# 04_Misc.net
KiCad netlist of a schematic drawn in Altium Designer
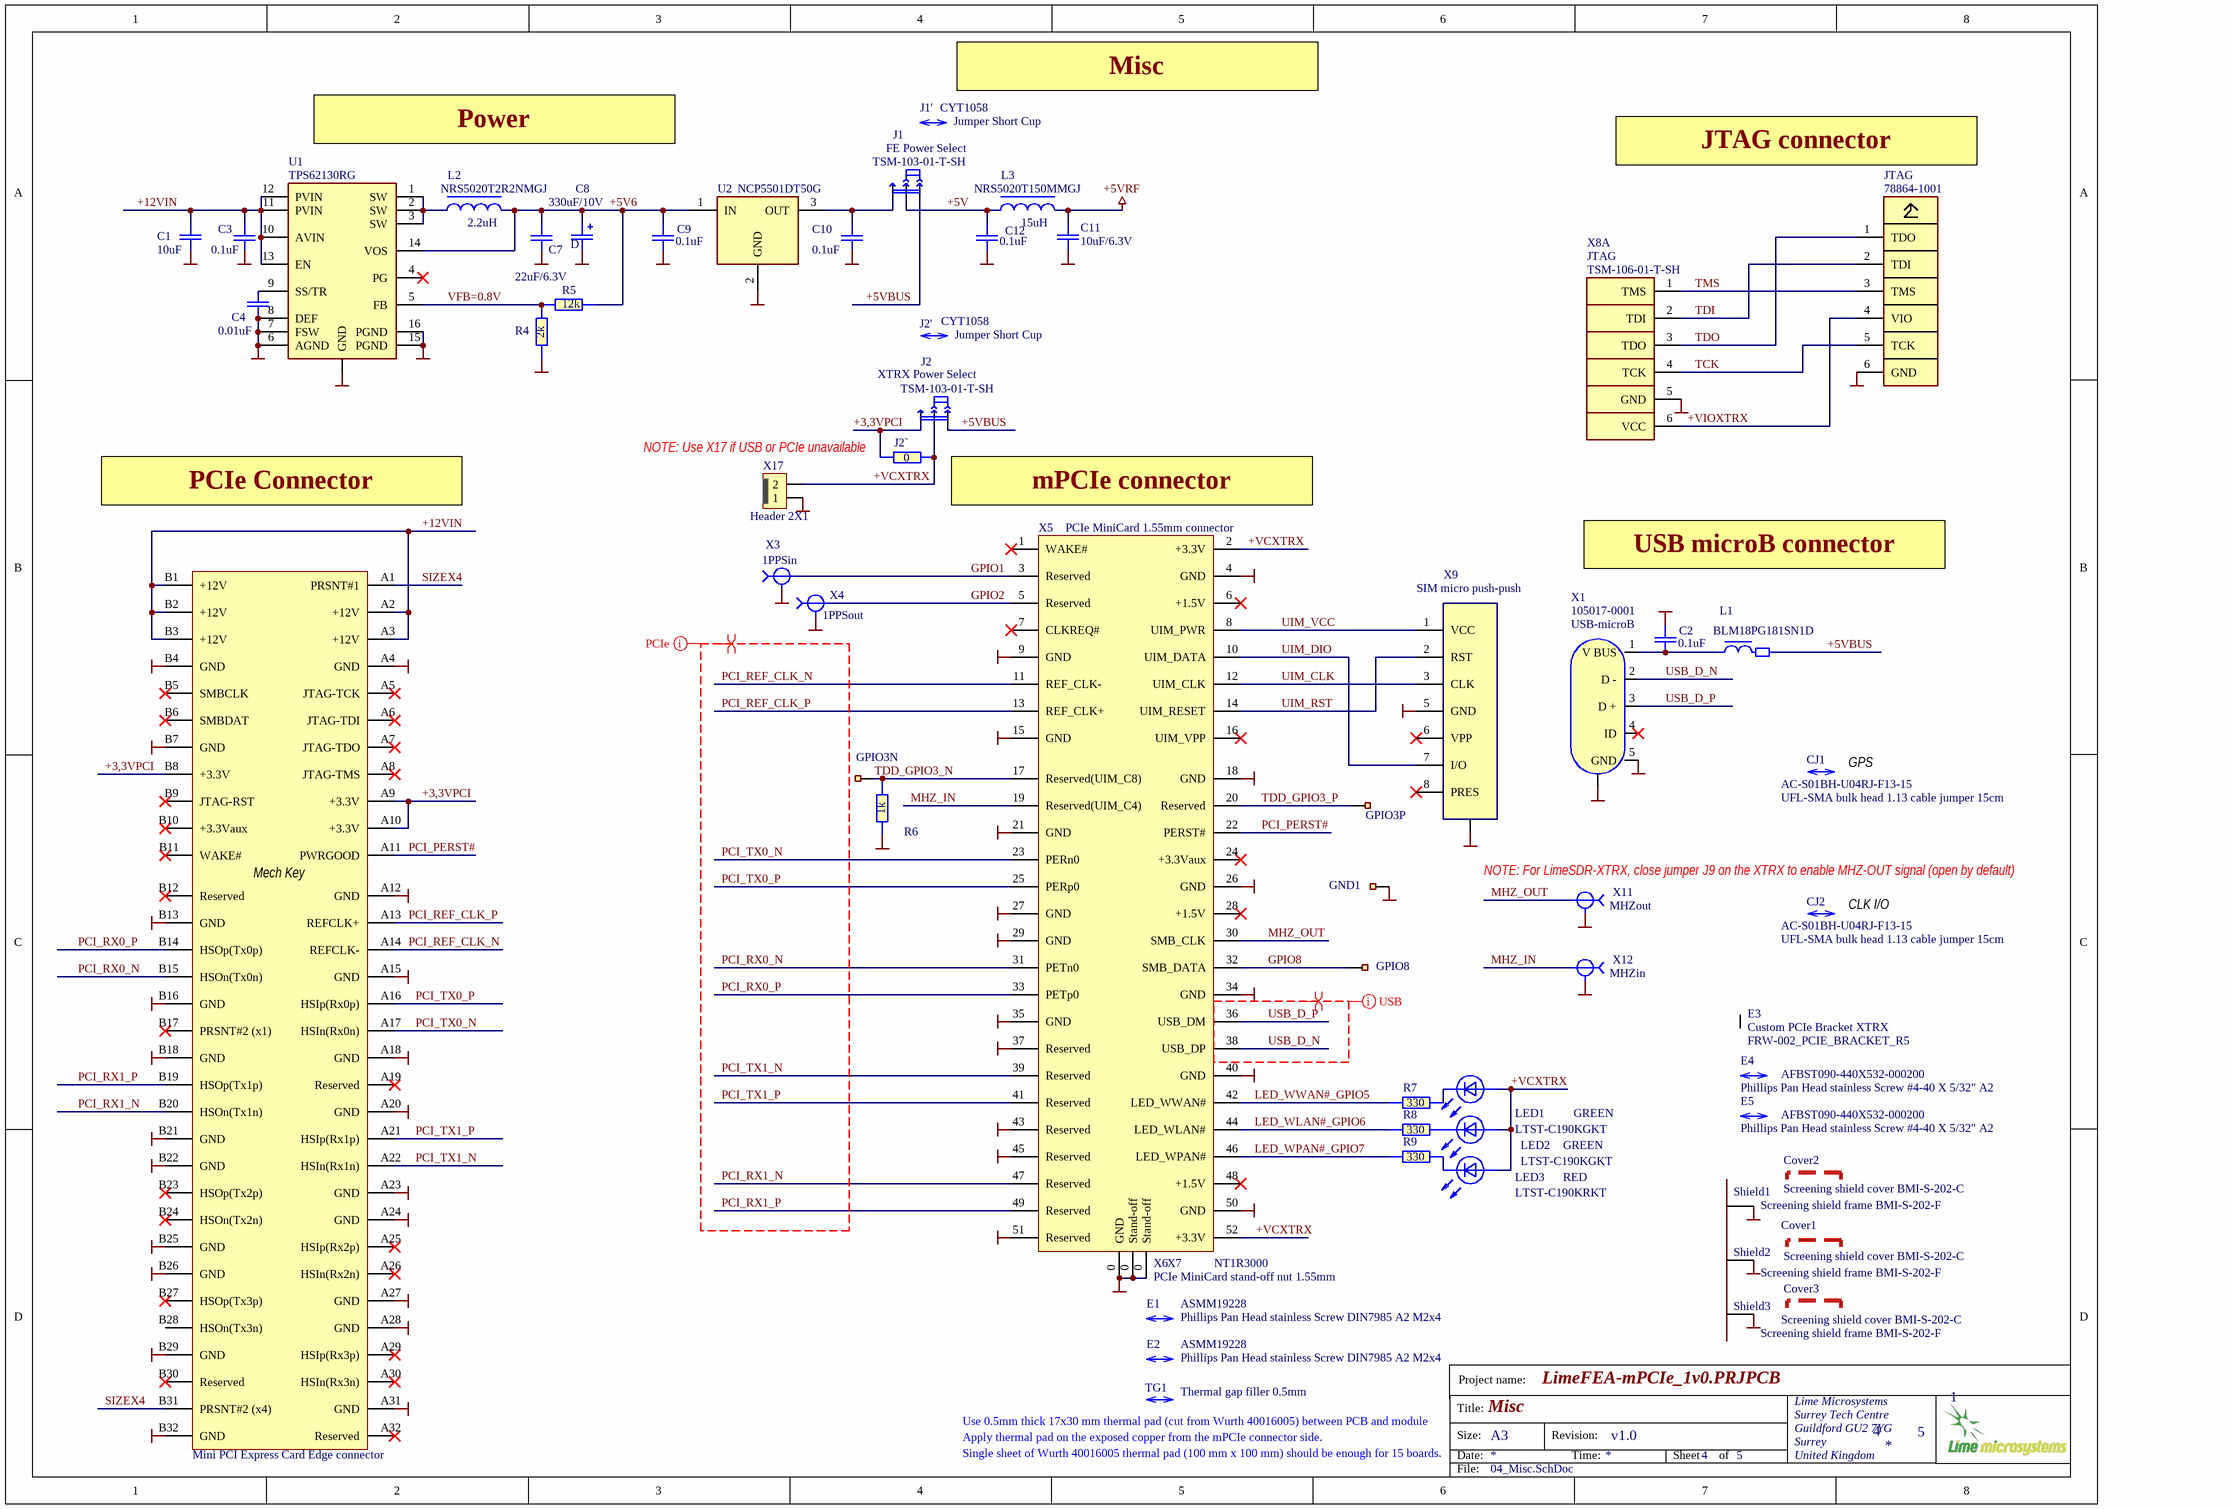
[diagram p0: 04_Misc.SchDoc]

(export (version "E")
  (design (tool "Eeschema 10.0.6"))
  (components
    (comp (ref "C1")
      (value "10uF")
      (footprint "C0805")
      (description "Capacitor")
      (fields (field (name "MANUFACTURER") "MURATA") (field (name "TOLERANCE") "20%"))
      (libsource (lib "Capacitors") (part "C0805"))
    )
    (comp (ref "C2")
      (value "0.1uF")
      (footprint "C0603-PHILLIPS")
      (description "Capacitor")
      (fields (field (name "MANUFACTURER") "MURATA") (field (name "TOLERANCE") "20%"))
      (libsource (lib "altium-import") (part "root_2_C0603_"))
    )
    (comp (ref "C3")
      (value "0.1uF")
      (footprint "C0603-PHILLIPS")
      (description "Capacitor")
      (fields (field (name "MANUFACTURER") "MURATA") (field (name "TOLERANCE") "20%"))
      (libsource (lib "altium-import") (part "root_2_C0603_"))
    )
    (comp (ref "C4")
      (value "0.01uF")
      (footprint "C0603-PHILLIPS")
      (description "Capacitor")
      (fields (field (name "MANUFACTURER") "MURATA") (field (name "TOLERANCE") "20%"))
      (libsource (lib "Capacitors") (part "C0603"))
    )
    (comp (ref "C7")
      (value "22uF/6.3V")
      (footprint "C0603-PHILLIPS")
      (description "Capacitor")
      (fields (field (name "MANUFACTURER") "MURATA") (field (name "TOLERANCE") "20%"))
      (libsource (lib "altium-import") (part "root_2_C0603_"))
    )
    (comp (ref "C8")
      (value "330uF/10V")
      (footprint "cd7343")
      (description "Capacitor")
      (fields (field (name "MANUFACTURER") "Kemet"))
      (libsource (lib "altium-import") (part "root_0_CD7343_"))
    )
    (comp (ref "C9")
      (value "0.1uF")
      (footprint "C0603-PHILLIPS")
      (description "Capacitor")
      (fields (field (name "MANUFACTURER") "MURATA") (field (name "TOLERANCE") "20%"))
      (libsource (lib "altium-import") (part "root_2_C0603_"))
    )
    (comp (ref "C10")
      (value "0.1uF")
      (footprint "C0603-PHILLIPS")
      (description "Capacitor")
      (fields (field (name "MANUFACTURER") "MURATA") (field (name "TOLERANCE") "20%"))
      (libsource (lib "altium-import") (part "root_2_C0603_"))
    )
    (comp (ref "C11")
      (value "10uF/6.3V")
      (footprint "C0603-Phillips")
      (description "Capacitor")
      (fields (field (name "MANUFACTURER") "MURATA") (field (name "TOLERANCE") "20%"))
      (libsource (lib "") (part "C0603_1"))
    )
    (comp (ref "C12")
      (value "0.1uF")
      (footprint "C0603-PHILLIPS")
      (description "Capacitor")
      (fields (field (name "MANUFACTURER") "MURATA") (field (name "TOLERANCE") "20%"))
      (libsource (lib "altium-import") (part "root_2_C0603_"))
    )
    (comp (ref "CJ1")
      (value "AC-S01BH-U04RJ-F13-15")
      (description "Cable jumper")
      (fields
        (field (name "MANUFACTURER") "RFSupplier")
        (field (name "MISC") "UFL-SMA bulk head 1.13 cable jumper 15cm")
      )
      (libsource (lib "LimeFEA-mPCIe_1v0") (part "Mating part"))
    )
    (comp (ref "CJ2")
      (value "AC-S01BH-U04RJ-F13-15")
      (description "Cable jumper")
      (fields
        (field (name "MANUFACTURER") "RFSupplier")
        (field (name "MISC") "UFL-SMA bulk head 1.13 cable jumper 15cm")
      )
      (libsource (lib "LimeFEA-mPCIe_1v0") (part "Mating part"))
    )
    (comp (ref "Cover1")
      (value "Screening shield cover BMI-S-202-C")
      (description "Screening shield cover")
      (fields (field (name "MANUFACTURER") "Laird Tech"))
      (libsource (lib "LimeFEA-mPCIe_1v0") (part "Screen cover BMI-S-202-C"))
    )
    (comp (ref "Cover2")
      (value "Screening shield cover BMI-S-202-C")
      (description "Screening shield cover")
      (fields (field (name "MANUFACTURER") "Laird Tech"))
      (libsource (lib "LimeFEA-mPCIe_1v0") (part "Screen cover BMI-S-202-C"))
    )
    (comp (ref "Cover3")
      (value "Screening shield cover BMI-S-202-C")
      (description "Screening shield cover")
      (fields (field (name "MANUFACTURER") "Laird Tech"))
      (libsource (lib "LimeFEA-mPCIe_1v0") (part "Screen cover BMI-S-202-C"))
    )
    (comp (ref "E1")
      (value "ASMM19228")
      (description "Screw M2")
      (fields
        (field (name "MANUFACTURER") "Aspen Fasteners")
        (field (name "MISC") "Phillips Pan Head stainless Screw DIN7985 A2 M2x4")
      )
      (libsource (lib "LimeFEA-mPCIe_1v0") (part "Mating subpart 1"))
    )
    (comp (ref "E2")
      (value "ASMM19228")
      (description "Screw M2")
      (fields
        (field (name "MANUFACTURER") "Aspen Fasteners")
        (field (name "MISC") "Phillips Pan Head stainless Screw DIN7985 A2 M2x4")
      )
      (libsource (lib "LimeFEA-mPCIe_1v0") (part "Mating subpart 1"))
    )
    (comp (ref "E3")
      (value "Custom PCIe Bracket XTRX")
      (footprint "Custom_PCIe_bracket_XTRX1")
      (description "CNC'ed enclosure component")
      (fields (field (name "ALTIUM_VALUE") "FRW-002_PCIE_BRACKET_R5"))
      (libsource (lib "LimeFEA-mPCIe_1v0") (part "PCI_Bracket_XTRX1"))
    )
    (comp (ref "E4")
      (value "AFBST090-440X532-000200")
      (description "Screw #4-40")
      (fields
        (field (name "MANUFACTURER") "Aspen Fasteners")
        (field (name "MISC") "Phillips Pan Head stainless Screw #4-40 X 5/32\" A2")
      )
      (libsource (lib "LimeFEA-mPCIe_1v0") (part "Mating subpart 1"))
    )
    (comp (ref "E5")
      (value "AFBST090-440X532-000200")
      (description "Screw #4-40")
      (fields
        (field (name "MANUFACTURER") "Aspen Fasteners")
        (field (name "MISC") "Phillips Pan Head stainless Screw #4-40 X 5/32\" A2")
      )
      (libsource (lib "LimeFEA-mPCIe_1v0") (part "Mating subpart 1"))
    )
    (comp (ref "GND1")
      (value "~")
      (footprint "KP-C_d1mm")
      (fields (field (name "MANUFACTURER") "PCB"))
      (libsource (lib "") (part "KP40X40_1"))
    )
    (comp (ref "GPIO3N")
      (value "~")
      (footprint "KP-C_d1mm")
      (fields (field (name "MANUFACTURER") "PCB"))
      (libsource (lib "") (part "KP40X40_1"))
    )
    (comp (ref "GPIO3P")
      (value "~")
      (footprint "KP-C_d1mm")
      (fields (field (name "MANUFACTURER") "PCB"))
      (libsource (lib "Connectors") (part "KP40X40"))
    )
    (comp (ref "GPIO8")
      (value "~")
      (footprint "KP-C_d1mm")
      (fields (field (name "MANUFACTURER") "PCB"))
      (libsource (lib "Connectors") (part "KP40X40"))
    )
    (comp (ref "J1")
      (value "TSM-103-01-T-SH")
      (footprint "Head_Male_3P_R/A_SMD")
      (description "Jumper 3 pin")
      (fields (field (name "MANUFACTURER") "Samtec") (field (name "ALTIUM_VALUE") "FE Power Select"))
      (libsource (lib "LimeFEA-mPCIe_1v0") (part "JUMPER_3P R/A SMD"))
    )
    (comp (ref "J1'")
      (value "CYT1058")
      (description "Jumper Short Cup")
      (fields (field (name "MISC") "Jumper Short Cup"))
      (libsource (lib "LimeFEA-mPCIe_1v0") (part "Mating part"))
    )
    (comp (ref "J2")
      (value "TSM-103-01-T-SH")
      (footprint "Head_Male_3P_R/A_SMD")
      (description "Jumper 3 pin")
      (fields (field (name "MANUFACTURER") "Samtec") (field (name "ALTIUM_VALUE") "XTRX Power Select"))
      (libsource (lib "LimeFEA-mPCIe_1v0") (part "JUMPER_3P R/A SMD"))
    )
    (comp (ref "J2'")
      (value "CYT1058")
      (description "Jumper Short Cup")
      (fields (field (name "MISC") "Jumper Short Cup"))
      (libsource (lib "Andy") (part "Mating part"))
    )
    (comp (ref "J2`")
      (value "0")
      (footprint "R0603-PHILLIPS")
      (description "Jumper")
      (fields (field (name "MANUFACTURER") "YAGEO") (field (name "TOLERANCE") "1%"))
      (libsource (lib "altium-import") (part "root_1_R0603_"))
    )
    (comp (ref "L1")
      (value "BLM18PG181SN1D")
      (footprint "TI160808-Phillips")
      (description "Ferrite Bead EMIFIL")
      (fields (field (name "MANUFACTURER") "MURATA"))
      (libsource (lib "LimeFEA-mPCIe_1v0") (part "EMI_BLM18"))
    )
    (comp (ref "L2")
      (value "2.2uH")
      (footprint "L-NRS5030")
      (description "Coil")
      (fields
        (field (name "MANUFACTURER") "Taiyo Yuden")
        (field (name "TOLERANCE") "20%")
        (field (name "NAME") "NRS5020T2R2NMGJ")
      )
      (libsource (lib "LimeFEA-mPCIe_1v0") (part "L-NRS50x0"))
    )
    (comp (ref "L3")
      (value "15uH")
      (footprint "L-NRS5030")
      (description "Coil")
      (fields
        (field (name "MANUFACTURER") "Taiyo Yuden")
        (field (name "TOLERANCE") "20%")
        (field (name "NAME") "NRS5020T150MMGJ")
      )
      (libsource (lib "LimeFEA-mPCIe_1v0") (part "L-NRS50x0"))
    )
    (comp (ref "LED1")
      (value "LTST-C190KGKT")
      (footprint "LED-0603GR")
      (description "LED GREEN")
      (fields (field (name "MANUFACTURER") "Lite-On Inc") (field (name "ALTIUM_VALUE") "GREEN"))
      (libsource (lib "LimeFEA-mPCIe_1v0") (part "LED0603GR_Lite-On"))
    )
    (comp (ref "LED2")
      (value "LTST-C190KGKT")
      (footprint "LED-0603GR")
      (description "LED GREEN")
      (fields (field (name "MANUFACTURER") "Lite-On Inc") (field (name "ALTIUM_VALUE") "GREEN"))
      (libsource (lib "LimeFEA-mPCIe_1v0") (part "LED0603GR_Lite-On"))
    )
    (comp (ref "LED3")
      (value "LTST-C190KRKT")
      (footprint "LED-0603RD")
      (description "LED RED")
      (fields (field (name "MANUFACTURER") "Lite-On Inc") (field (name "ALTIUM_VALUE") "RED"))
      (libsource (lib "LimeFEA-mPCIe_1v0") (part "LED0603RD_Lite-On"))
    )
    (comp (ref "R4")
      (value "2k")
      (footprint "R0603-PHILLIPS")
      (description "Resistor")
      (fields (field (name "MANUFACTURER") "YAGEO") (field (name "TOLERANCE") "1%"))
      (libsource (lib "") (part "R0603_1"))
    )
    (comp (ref "R5")
      (value "12k")
      (footprint "R0603-PHILLIPS")
      (description "Resistor")
      (fields (field (name "MANUFACTURER") "YAGEO") (field (name "TOLERANCE") "1%"))
      (libsource (lib "Resistors") (part "R0603"))
    )
    (comp (ref "R6")
      (value "1k")
      (footprint "R0603-PHILLIPS")
      (description "Resistor")
      (fields (field (name "MANUFACTURER") "YAGEO") (field (name "TOLERANCE") "1%"))
      (libsource (lib "altium-import") (part "root_2_R0603_"))
    )
    (comp (ref "R7")
      (value "330")
      (footprint "R0603-PHILLIPS")
      (description "Resistor")
      (fields (field (name "MANUFACTURER") "YAGEO") (field (name "TOLERANCE") "1%"))
      (libsource (lib "altium-import") (part "root_1_R0603_"))
    )
    (comp (ref "R8")
      (value "330")
      (footprint "R0603-PHILLIPS")
      (description "Resistor")
      (fields (field (name "MANUFACTURER") "YAGEO") (field (name "TOLERANCE") "1%"))
      (libsource (lib "altium-import") (part "root_1_R0603_"))
    )
    (comp (ref "R9")
      (value "330")
      (footprint "R0603-PHILLIPS")
      (description "Resistor")
      (fields (field (name "MANUFACTURER") "YAGEO") (field (name "TOLERANCE") "1%"))
      (libsource (lib "altium-import") (part "root_1_R0603_"))
    )
    (comp (ref "Shield1")
      (value "Screening shield frame BMI-S-202-F")
      (footprint "BMI-S-202-F")
      (description "Screening shield frame")
      (fields (field (name "MANUFACTURER") "Laird Tech"))
      (libsource (lib "LimeFEA-mPCIe_1v0") (part "Screen frame BMI-S-202-F"))
    )
    (comp (ref "Shield2")
      (value "Screening shield frame BMI-S-202-F")
      (footprint "BMI-S-202-F")
      (description "Screening shield frame")
      (fields (field (name "MANUFACTURER") "Laird Tech"))
      (libsource (lib "LimeFEA-mPCIe_1v0") (part "Screen frame BMI-S-202-F"))
    )
    (comp (ref "Shield3")
      (value "Screening shield frame BMI-S-202-F")
      (footprint "BMI-S-202-F")
      (description "Screening shield frame")
      (fields (field (name "MANUFACTURER") "Laird Tech"))
      (libsource (lib "LimeFEA-mPCIe_1v0") (part "Screen frame BMI-S-202-F"))
    )
    (comp (ref "TG1")
      (value "The thermal pad with a size of 100 mm x 100 mm is to be cut in 17 mm x 30 mm pieces (resulting in a possible total of 15 pcs. from a single whole pad). A single assembled PCB requires 1 pcs. of 17 mm x 30 mm pad per 1 board. Calculate the number of whole thermal pad (P/N 40016005) pieces based on the assembled board batch size, rounding this number to whole pad pieces. Example: 5 pcs. PCB batch requires 1 pcs. of thermal pad (P/N 40016005) with leftovers. 300 pcs. PCB batch requires 20 pcs. of thermal pads (P/N 40016005) without leftovers.")
      (description "Thermal gap filler")
      (fields
        (field (name "MANUFACTURER") "Würth Elektronik")
        (field (name "MISC") "Thermal gap filler 0.5mm")
      )
      (libsource (lib "LimeFEA-mPCIe_1v0") (part "Mating subpart 1"))
    )
    (comp (ref "U1")
      (value "TPS62130RG")
      (footprint "QFN16(3x3/0/5mm)-Case485AE")
      (description "IC")
      (fields (field (name "MANUFACTURER") "TI"))
      (libsource (lib "LimeFEA-mPCIe_1v0") (part "TPS6213x"))
    )
    (comp (ref "U2")
      (value "NCP5501DT50G")
      (footprint "DPAK-3")
      (description "IC LDO fixed Vo")
      (fields (field (name "MANUFACTURER") "ON Semi"))
      (libsource (lib "LimeFEA-mPCIe_1v0") (part "NCP5501DTxxG"))
    )
    (comp (ref "X1")
      (value "105017-0001")
      (footprint "USB-micro-B")
      (description "Connector microUSB-B")
      (fields (field (name "MANUFACTURER") "MOLEX") (field (name "NAME") "USB-microB"))
      (libsource (lib "LimeFEA-mPCIe_1v0") (part "USB-microB_105017-1"))
    )
    (comp (ref "X2")
      (value "Mini PCI Express Card Edge connector")
      (footprint "PCIe x4 edge connector")
      (description "PCIe x4 Card edge connector")
      (libsource (lib "LimeFEA-mPCIe_1v0") (part "PCIe x4 Card"))
    )
    (comp (ref "X3")
      (value "0734120110")
      (footprint "U_FL")
      (description "Connector (UMCC)")
      (fields (field (name "MANUFACTURER") "Molex") (field (name "MISC") "1PPSin"))
      (libsource (lib "LimeFEA-mPCIe_1v0") (part "U_FL"))
    )
    (comp (ref "X4")
      (value "0734120110")
      (footprint "U_FL")
      (description "Connector (UMCC)")
      (fields (field (name "MANUFACTURER") "Molex") (field (name "MISC") "1PPSout"))
      (libsource (lib "LimeFEA-mPCIe_1v0") (part "U_FL"))
    )
    (comp (ref "X5")
      (value "PCIe MiniCard 1.55mm connector")
      (footprint "PCIe MiniCard 1.55mm conn")
      (description "Connector PCIe MiniCard")
      (fields (field (name "MANUFACTURER") "JAE Electronics"))
      (libsource (lib "LimeFEA-mPCIe_1v0") (part "PCIe MiniCard conn h1.55mm"))
    )
    (comp (ref "X6")
      (value "NT1R3000")
      (footprint "PCIe MiniCard 1.55mm stand off nut")
      (description "Stand-off nut PCIe MiniCard")
      (fields
        (field (name "MANUFACTURER") "JAE Electronics")
        (field (name "MISC") "PCIe MiniCard stand-off nut 1.55mm")
      )
      (libsource (lib "LimeFEA-mPCIe_1v0") (part "PCIe MiniCard nut h1.55mm"))
    )
    (comp (ref "X7")
      (value "NT1R3000")
      (footprint "PCIe MiniCard 1.55mm stand off nut")
      (description "Stand-off nut PCIe MiniCard")
      (fields (field (name "MANUFACTURER") "JAE Electronics"))
      (libsource (lib "LimeFEA-mPCIe_1v0") (part "PCIe MiniCard nut h1.55mm"))
    )
    (comp (ref "X8")
      (value "TSM-106-01-T-SH")
      (footprint "Head_Male_6P_R/A_SMD")
      (description "Connector header male")
      (fields (field (name "MANUFACTURER") "Samtec") (field (name "ALTIUM_VALUE") "JTAG"))
      (libsource (lib "LimeFEA-mPCIe_1v0") (part "Conn TSM-106-01-T-SH (=M20-89605)"))
    )
    (comp (ref "X9")
      (value "SIM micro push-push")
      (footprint "SIM_SF56S006V4BR2000-dig")
      (description "Connector SIM micro card")
      (fields (field (name "MANUFACTURER") "JAE"))
      (libsource (lib "LimeFEA-mPCIe_1v0") (part "SIM micro push-push"))
    )
    (comp (ref "X10")
      (value "JTAG")
      (footprint "Molex 78864-1001")
      (description "Connector board to board")
      (fields (field (name "MANUFACTURER") "Molex") (field (name "NAME") "78864-1001"))
      (libsource (lib "LimeFEA-mPCIe_1v0") (part "Conn Molex_788641001"))
    )
    (comp (ref "X11")
      (value "0734120110")
      (footprint "U_FL")
      (description "Connector (UMCC)")
      (fields (field (name "MANUFACTURER") "Molex") (field (name "MISC") "MHZout"))
      (libsource (lib "LimeFEA-mPCIe_1v0") (part "U_FL"))
    )
    (comp (ref "X12")
      (value "0734120110")
      (footprint "U_FL")
      (description "Connector (UMCC)")
      (fields (field (name "MANUFACTURER") "Molex") (field (name "MISC") "MHZin"))
      (libsource (lib "LimeFEA-mPCIe_1v0") (part "U_FL"))
    )
    (comp (ref "X17")
      (value "Header 2X1")
      (footprint "Header1x2_TH_LOCKING")
      (description "Headers & Wire Housings KK 100 Hdr FrLk Vert 02 Ckt Gold")
      (fields (field (name "MANUFACTURER PART NUMBER") "22-11-2026") (field (name "MANUFACTURER") "Molex"))
      (libsource (lib "LimeMicroAltiumLib_schLib_r04") (part "Header 2X1 LOCK"))
    )
  )
  (nets
    (net (code "1") (name "+5VRF") (class "Default")
      (node (ref "C11") (pin "2") (pinfunction "2_2") (pintype "passive"))
      (node (ref "L3") (pin "2") (pinfunction "2_2") (pintype "passive"))
    )
    (net (code "2") (name "/+3,3VPCI") (class "Default")
      (node (ref "J2") (pin "3") (pinfunction "3_3") (pintype "passive"))
      (node (ref "J2`") (pin "1") (pinfunction "1_1") (pintype "passive"))
      (node (ref "X2") (pin "A10") (pinfunction "+3.3V_A10") (pintype "passive"))
      (node (ref "X2") (pin "A9") (pinfunction "+3.3V_A9") (pintype "passive"))
      (node (ref "X2") (pin "B8") (pinfunction "+3.3V_B8") (pintype "passive"))
    )
    (net (code "3") (name "/+5V") (class "Default")
      (node (ref "C12") (pin "2") (pinfunction "2_2") (pintype "passive"))
      (node (ref "J1") (pin "2") (pinfunction "2_2") (pintype "passive"))
      (node (ref "L3") (pin "1") (pinfunction "1_1") (pintype "passive"))
    )
    (net (code "4") (name "/+5V6") (class "Default")
      (node (ref "C7") (pin "2") (pinfunction "2_2") (pintype "passive"))
      (node (ref "C8") (pin "1") (pinfunction "+_1") (pintype "passive"))
      (node (ref "C9") (pin "2") (pinfunction "2_2") (pintype "passive"))
      (node (ref "L2") (pin "2") (pinfunction "2_2") (pintype "passive"))
      (node (ref "R5") (pin "2") (pinfunction "2_2") (pintype "passive"))
      (node (ref "U1") (pin "14") (pinfunction "VOS_14") (pintype "passive"))
      (node (ref "U2") (pin "1") (pinfunction "IN_1") (pintype "passive"))
    )
    (net (code "5") (name "/+5VBUS") (class "Default")
      (node (ref "J1") (pin "1") (pinfunction "1_1") (pintype "passive"))
      (node (ref "J2") (pin "1") (pinfunction "1_1") (pintype "passive"))
      (node (ref "L1") (pin "2") (pinfunction "2_2") (pintype "passive"))
    )
    (net (code "6") (name "/+12VIN") (class "Default")
      (node (ref "C1") (pin "1") (pinfunction "1_1") (pintype "passive"))
      (node (ref "C3") (pin "2") (pinfunction "2_2") (pintype "passive"))
      (node (ref "U1") (pin "10") (pinfunction "AVIN_10") (pintype "passive"))
      (node (ref "U1") (pin "11") (pinfunction "PVIN_11") (pintype "passive"))
      (node (ref "U1") (pin "12") (pinfunction "PVIN_12") (pintype "passive"))
      (node (ref "U1") (pin "13") (pinfunction "EN_13") (pintype "passive"))
      (node (ref "X2") (pin "A2") (pinfunction "+12V_A2") (pintype "passive"))
      (node (ref "X2") (pin "A3") (pinfunction "+12V_A3") (pintype "passive"))
      (node (ref "X2") (pin "B1") (pinfunction "+12V_B1") (pintype "passive"))
      (node (ref "X2") (pin "B2") (pinfunction "+12V_B2") (pintype "passive"))
      (node (ref "X2") (pin "B3") (pinfunction "+12V_B3") (pintype "passive"))
    )
    (net (code "7") (name "/+VCXTRX") (class "Default")
      (node (ref "J2") (pin "2") (pinfunction "2_2") (pintype "passive"))
      (node (ref "J2`") (pin "2") (pinfunction "2_2") (pintype "passive"))
      (node (ref "LED1") (pin "2") (pinfunction "A_2") (pintype "passive"))
      (node (ref "LED2") (pin "2") (pinfunction "A_2") (pintype "passive"))
      (node (ref "LED3") (pin "2") (pinfunction "A_2") (pintype "passive"))
      (node (ref "X17") (pin "2") (pinfunction "2_2") (pintype "passive"))
      (node (ref "X5") (pin "2") (pinfunction "+3.3V_2") (pintype "passive"))
      (node (ref "X5") (pin "52") (pinfunction "+3.3V_52") (pintype "passive"))
    )
    (net (code "8") (name "/+VIOXTRX") (class "Default")
      (node (ref "X10") (pin "4") (pinfunction "VIO_4") (pintype "passive"))
      (node (ref "X8") (pin "6") (pinfunction "TMS_6") (pintype "passive"))
    )
    (net (code "9") (name "/GPIO1") (class "Default")
      (node (ref "X3") (pin "1") (pinfunction "1_1") (pintype "passive"))
      (node (ref "X5") (pin "3") (pinfunction "Reserved_3") (pintype "passive"))
    )
    (net (code "10") (name "/GPIO2") (class "Default")
      (node (ref "X4") (pin "1") (pinfunction "1_1") (pintype "passive"))
      (node (ref "X5") (pin "5") (pinfunction "Reserved_5") (pintype "passive"))
    )
    (net (code "11") (name "/GPIO8") (class "Default")
      (node (ref "GPIO8") (pin "1") (pinfunction "1_1") (pintype "passive"))
      (node (ref "X5") (pin "32") (pinfunction "SMB_DATA_32") (pintype "passive"))
    )
    (net (code "12") (name "/LED_WLAN#_GPIO6") (class "Default")
      (node (ref "R8") (pin "1") (pinfunction "1_1") (pintype "passive"))
      (node (ref "X5") (pin "44") (pinfunction "LED_WLAN#_44") (pintype "passive"))
    )
    (net (code "13") (name "/LED_WPAN#_GPIO7") (class "Default")
      (node (ref "R9") (pin "1") (pinfunction "1_1") (pintype "passive"))
      (node (ref "X5") (pin "46") (pinfunction "LED_WPAN#_46") (pintype "passive"))
    )
    (net (code "14") (name "/LED_WWAN#_GPIO5") (class "Default")
      (node (ref "R7") (pin "1") (pinfunction "1_1") (pintype "passive"))
      (node (ref "X5") (pin "42") (pinfunction "LED_WWAN#_42") (pintype "passive"))
    )
    (net (code "15") (name "/MHZ_IN") (class "Default")
      (node (ref "X12") (pin "1") (pinfunction "1_1") (pintype "passive"))
      (node (ref "X5") (pin "19") (pinfunction "Reserved(UIM_C4)_19") (pintype "passive"))
    )
    (net (code "16") (name "/MHZ_OUT") (class "Default")
      (node (ref "X11") (pin "1") (pinfunction "1_1") (pintype "passive"))
      (node (ref "X5") (pin "30") (pinfunction "SMB_CLK_30") (pintype "passive"))
    )
    (net (code "17") (name "/PCI_PERST#") (class "Default")
      (node (ref "X2") (pin "A11") (pinfunction "PWRGOOD_A11") (pintype "passive"))
      (node (ref "X5") (pin "22") (pinfunction "PERST#_22") (pintype "passive"))
    )
    (net (code "18") (name "/PCI_REF_CLK_N") (class "Default")
      (node (ref "X2") (pin "A14") (pinfunction "REFCLK-_A14") (pintype "passive"))
      (node (ref "X5") (pin "11") (pinfunction "REF_CLK-_11") (pintype "passive"))
    )
    (net (code "19") (name "/PCI_REF_CLK_P") (class "Default")
      (node (ref "X2") (pin "A13") (pinfunction "REFCLK+_A13") (pintype "passive"))
      (node (ref "X5") (pin "13") (pinfunction "REF_CLK+_13") (pintype "passive"))
    )
    (net (code "20") (name "/PCI_RX0_N") (class "Default")
      (node (ref "X2") (pin "B15") (pinfunction "HSOn(Tx0n)_B15") (pintype "passive"))
      (node (ref "X5") (pin "31") (pinfunction "PETn0_31") (pintype "passive"))
    )
    (net (code "21") (name "/PCI_RX0_P") (class "Default")
      (node (ref "X2") (pin "B14") (pinfunction "HSOp(Tx0p)_B14") (pintype "passive"))
      (node (ref "X5") (pin "33") (pinfunction "PETp0_33") (pintype "passive"))
    )
    (net (code "22") (name "/PCI_RX1_N") (class "Default")
      (node (ref "X2") (pin "B20") (pinfunction "HSOn(Tx1n)_B20") (pintype "passive"))
      (node (ref "X5") (pin "47") (pinfunction "Reserved_47") (pintype "passive"))
    )
    (net (code "23") (name "/PCI_RX1_P") (class "Default")
      (node (ref "X2") (pin "B19") (pinfunction "HSOp(Tx1p)_B19") (pintype "passive"))
      (node (ref "X5") (pin "49") (pinfunction "Reserved_49") (pintype "passive"))
    )
    (net (code "24") (name "/PCI_TX0_N") (class "Default")
      (node (ref "X2") (pin "A17") (pinfunction "HSIn(Rx0n)_A17") (pintype "passive"))
      (node (ref "X5") (pin "23") (pinfunction "PERn0_23") (pintype "passive"))
    )
    (net (code "25") (name "/PCI_TX0_P") (class "Default")
      (node (ref "X2") (pin "A16") (pinfunction "HSIp(Rx0p)_A16") (pintype "passive"))
      (node (ref "X5") (pin "25") (pinfunction "PERp0_25") (pintype "passive"))
    )
    (net (code "26") (name "/PCI_TX1_N") (class "Default")
      (node (ref "X2") (pin "A22") (pinfunction "HSIn(Rx1n)_A22") (pintype "passive"))
      (node (ref "X5") (pin "39") (pinfunction "Reserved_39") (pintype "passive"))
    )
    (net (code "27") (name "/PCI_TX1_P") (class "Default")
      (node (ref "X2") (pin "A21") (pinfunction "HSIp(Rx1p)_A21") (pintype "passive"))
      (node (ref "X5") (pin "41") (pinfunction "Reserved_41") (pintype "passive"))
    )
    (net (code "28") (name "/SIZEX4") (class "Default")
      (node (ref "X2") (pin "A1") (pinfunction "PRSNT#1_A1") (pintype "passive"))
      (node (ref "X2") (pin "B31") (pinfunction "PRSNT#2_(x4)_B31") (pintype "passive"))
    )
    (net (code "29") (name "/TCK") (class "Default")
      (node (ref "X10") (pin "5") (pinfunction "TCK_5") (pintype "passive"))
      (node (ref "X8") (pin "4") (pinfunction "TCK_4") (pintype "passive"))
    )
    (net (code "30") (name "/TDD_GPIO3_N") (class "Default")
      (node (ref "GPIO3N") (pin "1") (pinfunction "1_1") (pintype "passive"))
      (node (ref "R6") (pin "2") (pinfunction "2_2") (pintype "passive"))
      (node (ref "X5") (pin "17") (pinfunction "Reserved(UIM_C8)_17") (pintype "passive"))
    )
    (net (code "31") (name "/TDD_GPIO3_P") (class "Default")
      (node (ref "GPIO3P") (pin "1") (pinfunction "1_1") (pintype "passive"))
      (node (ref "X5") (pin "20") (pinfunction "Reserved_20") (pintype "passive"))
    )
    (net (code "32") (name "/TDI") (class "Default")
      (node (ref "X10") (pin "2") (pinfunction "TDI_2") (pintype "passive"))
      (node (ref "X8") (pin "2") (pinfunction "GND_2") (pintype "passive"))
    )
    (net (code "33") (name "/TDO") (class "Default")
      (node (ref "X10") (pin "1") (pinfunction "TDO_1") (pintype "passive"))
      (node (ref "X8") (pin "3") (pinfunction "TCK_3") (pintype "passive"))
    )
    (net (code "34") (name "/TMS") (class "Default")
      (node (ref "X10") (pin "3") (pinfunction "TMS_3") (pintype "passive"))
      (node (ref "X8") (pin "1") (pinfunction "VCC_1") (pintype "passive"))
    )
    (net (code "35") (name "/UIM_CLK") (class "Default")
      (node (ref "X5") (pin "12") (pinfunction "UIM_CLK_12") (pintype "passive"))
      (node (ref "X9") (pin "3") (pinfunction "CLK_3") (pintype "passive"))
    )
    (net (code "36") (name "/UIM_DIO") (class "Default")
      (node (ref "X5") (pin "10") (pinfunction "UIM_DATA_10") (pintype "passive"))
      (node (ref "X9") (pin "7") (pinfunction "I/O_7") (pintype "passive"))
    )
    (net (code "37") (name "/UIM_RST") (class "Default")
      (node (ref "X5") (pin "14") (pinfunction "UIM_RESET_14") (pintype "passive"))
      (node (ref "X9") (pin "2") (pinfunction "RST_2") (pintype "passive"))
    )
    (net (code "38") (name "/UIM_VCC") (class "Default")
      (node (ref "X5") (pin "8") (pinfunction "UIM_PWR_8") (pintype "passive"))
      (node (ref "X9") (pin "1") (pinfunction "VCC_1") (pintype "passive"))
    )
    (net (code "39") (name "/USB_D_N") (class "Default")
      (node (ref "X1") (pin "2") (pinfunction "D_-_2") (pintype "passive"))
      (node (ref "X5") (pin "38") (pinfunction "USB_DP_38") (pintype "passive"))
    )
    (net (code "40") (name "/USB_D_P") (class "Default")
      (node (ref "X1") (pin "3") (pinfunction "D_+_3") (pintype "passive"))
      (node (ref "X5") (pin "36") (pinfunction "USB_DM_36") (pintype "passive"))
    )
    (net (code "41") (name "GND") (class "Default")
      (node (ref "C1") (pin "2") (pinfunction "2_2") (pintype "passive"))
      (node (ref "C10") (pin "1") (pinfunction "1_1") (pintype "passive"))
      (node (ref "C11") (pin "1") (pinfunction "1_1") (pintype "passive"))
      (node (ref "C12") (pin "1") (pinfunction "1_1") (pintype "passive"))
      (node (ref "C2") (pin "2") (pinfunction "2_2") (pintype "passive"))
      (node (ref "C3") (pin "1") (pinfunction "1_1") (pintype "passive"))
      (node (ref "C4") (pin "2") (pinfunction "2_2") (pintype "passive"))
      (node (ref "C7") (pin "1") (pinfunction "1_1") (pintype "passive"))
      (node (ref "C8") (pin "2") (pinfunction "-_2") (pintype "passive"))
      (node (ref "C9") (pin "1") (pinfunction "1_1") (pintype "passive"))
      (node (ref "GND1") (pin "1") (pinfunction "1_1") (pintype "passive"))
      (node (ref "R4") (pin "2") (pinfunction "2_2") (pintype "passive"))
      (node (ref "R6") (pin "1") (pinfunction "1_1") (pintype "passive"))
      (node (ref "Shield1") (pin "0") (pinfunction "GND_0") (pintype "passive"))
      (node (ref "Shield2") (pin "0") (pinfunction "GND_0") (pintype "passive"))
      (node (ref "Shield3") (pin "0") (pinfunction "GND_0") (pintype "passive"))
      (node (ref "U1") (pin "0") (pinfunction "GND_0") (pintype "passive"))
      (node (ref "U1") (pin "15") (pinfunction "PGND_15") (pintype "passive"))
      (node (ref "U1") (pin "16") (pinfunction "PGND_16") (pintype "passive"))
      (node (ref "U1") (pin "6") (pinfunction "AGND_6") (pintype "passive"))
      (node (ref "U1") (pin "7") (pinfunction "FSW_7") (pintype "passive"))
      (node (ref "U1") (pin "8") (pinfunction "DEF_8") (pintype "passive"))
      (node (ref "U2") (pin "2") (pinfunction "GND_2") (pintype "passive"))
      (node (ref "X1") (pin "0") (pinfunction "GND_0") (pintype "passive"))
      (node (ref "X1") (pin "5") (pinfunction "GND_5") (pintype "passive"))
      (node (ref "X10") (pin "6") (pinfunction "GND_6") (pintype "passive"))
      (node (ref "X11") (pin "2") (pinfunction "GND_2") (pintype "passive"))
      (node (ref "X12") (pin "2") (pinfunction "GND_2") (pintype "passive"))
      (node (ref "X17") (pin "1") (pinfunction "1_1") (pintype "passive"))
      (node (ref "X2") (pin "A12") (pinfunction "GND_A12") (pintype "passive"))
      (node (ref "X2") (pin "A15") (pinfunction "GND_A15") (pintype "passive"))
      (node (ref "X2") (pin "A18") (pinfunction "GND_A18") (pintype "passive"))
      (node (ref "X2") (pin "A20") (pinfunction "GND_A20") (pintype "passive"))
      (node (ref "X2") (pin "A23") (pinfunction "GND_A23") (pintype "passive"))
      (node (ref "X2") (pin "A24") (pinfunction "GND_A24") (pintype "passive"))
      (node (ref "X2") (pin "A27") (pinfunction "GND_A27") (pintype "passive"))
      (node (ref "X2") (pin "A28") (pinfunction "GND_A28") (pintype "passive"))
      (node (ref "X2") (pin "A31") (pinfunction "GND_A31") (pintype "passive"))
      (node (ref "X2") (pin "A4") (pinfunction "GND_A4") (pintype "passive"))
      (node (ref "X2") (pin "B13") (pinfunction "GND_B13") (pintype "passive"))
      (node (ref "X2") (pin "B16") (pinfunction "GND_B16") (pintype "passive"))
      (node (ref "X2") (pin "B18") (pinfunction "GND_B18") (pintype "passive"))
      (node (ref "X2") (pin "B21") (pinfunction "GND_B21") (pintype "passive"))
      (node (ref "X2") (pin "B22") (pinfunction "GND_B22") (pintype "passive"))
      (node (ref "X2") (pin "B25") (pinfunction "GND_B25") (pintype "passive"))
      (node (ref "X2") (pin "B26") (pinfunction "GND_B26") (pintype "passive"))
      (node (ref "X2") (pin "B29") (pinfunction "GND_B29") (pintype "passive"))
      (node (ref "X2") (pin "B32") (pinfunction "GND_B32") (pintype "passive"))
      (node (ref "X2") (pin "B4") (pinfunction "GND_B4") (pintype "passive"))
      (node (ref "X2") (pin "B7") (pinfunction "GND_B7") (pintype "passive"))
      (node (ref "X3") (pin "2") (pinfunction "GND_2") (pintype "passive"))
      (node (ref "X4") (pin "2") (pinfunction "GND_2") (pintype "passive"))
      (node (ref "X5") (pin "0") (pinfunction "GND_0") (pintype "passive"))
      (node (ref "X5") (pin "15") (pinfunction "GND_15") (pintype "passive"))
      (node (ref "X5") (pin "18") (pinfunction "GND_18") (pintype "passive"))
      (node (ref "X5") (pin "21") (pinfunction "GND_21") (pintype "passive"))
      (node (ref "X5") (pin "26") (pinfunction "GND_26") (pintype "passive"))
      (node (ref "X5") (pin "27") (pinfunction "GND_27") (pintype "passive"))
      (node (ref "X5") (pin "29") (pinfunction "GND_29") (pintype "passive"))
      (node (ref "X5") (pin "34") (pinfunction "GND_34") (pintype "passive"))
      (node (ref "X5") (pin "35") (pinfunction "GND_35") (pintype "passive"))
      (node (ref "X5") (pin "37") (pinfunction "Reserved_37") (pintype "passive"))
      (node (ref "X5") (pin "4") (pinfunction "GND_4") (pintype "passive"))
      (node (ref "X5") (pin "40") (pinfunction "GND_40") (pintype "passive"))
      (node (ref "X5") (pin "43") (pinfunction "Reserved_43") (pintype "passive"))
      (node (ref "X5") (pin "45") (pinfunction "Reserved_45") (pintype "passive"))
      (node (ref "X5") (pin "50") (pinfunction "GND_50") (pintype "passive"))
      (node (ref "X5") (pin "51") (pinfunction "Reserved_51") (pintype "passive"))
      (node (ref "X5") (pin "9") (pinfunction "GND_9") (pintype "passive"))
      (node (ref "X6") (pin "0") (pinfunction "Stand-off_0") (pintype "passive"))
      (node (ref "X7") (pin "0") (pinfunction "Stand-off_0") (pintype "passive"))
      (node (ref "X8") (pin "5") (pinfunction "TDI_5") (pintype "passive"))
      (node (ref "X9") (pin "0") (pinfunction "GND_0") (pintype "passive"))
      (node (ref "X9") (pin "5") (pinfunction "GND_5") (pintype "passive"))
    )
    (net (code "42") (name "Net-(L2-Pad1)") (class "Default")
      (node (ref "L2") (pin "1") (pinfunction "1_1") (pintype "passive"))
      (node (ref "U1") (pin "1") (pinfunction "SW_1") (pintype "passive"))
      (node (ref "U1") (pin "2") (pinfunction "SW_2") (pintype "passive"))
      (node (ref "U1") (pin "3") (pinfunction "SW_3") (pintype "passive"))
    )
    (net (code "43") (name "Net-(LED1-K)") (class "Default")
      (node (ref "LED1") (pin "1") (pinfunction "K_1") (pintype "passive"))
      (node (ref "R7") (pin "2") (pinfunction "2_2") (pintype "passive"))
    )
    (net (code "44") (name "Net-(LED2-K)") (class "Default")
      (node (ref "LED2") (pin "1") (pinfunction "K_1") (pintype "passive"))
      (node (ref "R8") (pin "2") (pinfunction "2_2") (pintype "passive"))
    )
    (net (code "45") (name "Net-(LED3-K)") (class "Default")
      (node (ref "LED3") (pin "1") (pinfunction "K_1") (pintype "passive"))
      (node (ref "R9") (pin "2") (pinfunction "2_2") (pintype "passive"))
    )
    (net (code "46") (name "Net-(U1-FB)") (class "Default")
      (node (ref "R4") (pin "1") (pinfunction "1_1") (pintype "passive"))
      (node (ref "R5") (pin "1") (pinfunction "1_1") (pintype "passive"))
      (node (ref "U1") (pin "5") (pinfunction "FB_5") (pintype "passive"))
    )
    (net (code "47") (name "Net-(U1-SS{slash}TR)") (class "Default")
      (node (ref "C4") (pin "1") (pinfunction "1_1") (pintype "passive"))
      (node (ref "U1") (pin "9") (pinfunction "SS/TR_9") (pintype "passive"))
    )
    (net (code "48") (name "Net-(U2-OUT)") (class "Default")
      (node (ref "C10") (pin "2") (pinfunction "2_2") (pintype "passive"))
      (node (ref "J1") (pin "3") (pinfunction "3_3") (pintype "passive"))
      (node (ref "U2") (pin "3") (pinfunction "OUT_3") (pintype "passive"))
    )
    (net (code "49") (name "Net-(X1-V_BUS)") (class "Default")
      (node (ref "C2") (pin "1") (pinfunction "1_1") (pintype "passive"))
      (node (ref "L1") (pin "1") (pinfunction "1_1") (pintype "passive"))
      (node (ref "X1") (pin "1") (pinfunction "V_BUS_1") (pintype "power_in"))
    )
    (net (code "50") (name "unconnected-(CJ1-Pad)") (class "Default")
      (node (ref "CJ1") (pin "") (pintype "passive"))
    )
    (net (code "51") (name "unconnected-(CJ2-Pad)") (class "Default")
      (node (ref "CJ2") (pin "") (pintype "passive"))
    )
    (net (code "52") (name "unconnected-(E1-Pad)") (class "Default")
      (node (ref "E1") (pin "") (pintype "passive"))
    )
    (net (code "53") (name "unconnected-(E2-Pad)") (class "Default")
      (node (ref "E2") (pin "") (pintype "passive"))
    )
    (net (code "54") (name "unconnected-(E3-Pad0)") (class "Default")
      (node (ref "E3") (pin "0") (pinfunction "0_0") (pintype "passive"))
    )
    (net (code "55") (name "unconnected-(E4-Pad)") (class "Default")
      (node (ref "E4") (pin "") (pintype "passive"))
    )
    (net (code "56") (name "unconnected-(E5-Pad)") (class "Default")
      (node (ref "E5") (pin "") (pintype "passive"))
    )
    (net (code "57") (name "unconnected-(J1'-Pad)") (class "Default")
      (node (ref "J1'") (pin "") (pintype "passive"))
    )
    (net (code "58") (name "unconnected-(J2'-Pad)") (class "Default")
      (node (ref "J2'") (pin "") (pintype "passive"))
    )
    (net (code "59") (name "unconnected-(TG1-Pad)") (class "Default")
      (node (ref "TG1") (pin "") (pintype "passive"))
    )
    (net (code "60") (name "unconnected-(U1-PG-Pad4)") (class "Default")
      (node (ref "U1") (pin "4") (pinfunction "PG_4") (pintype "passive+no_connect"))
    )
    (net (code "61") (name "unconnected-(X1-ID-Pad4)") (class "Default")
      (node (ref "X1") (pin "4") (pinfunction "ID_4") (pintype "passive+no_connect"))
    )
    (net (code "62") (name "unconnected-(X2-+3.3Vaux-PadB10)") (class "Default")
      (node (ref "X2") (pin "B10") (pinfunction "+3.3Vaux_B10") (pintype "passive+no_connect"))
    )
    (net (code "63") (name "unconnected-(X2-HSIn(Rx2n)-PadA26)") (class "Default")
      (node (ref "X2") (pin "A26") (pinfunction "HSIn(Rx2n)_A26") (pintype "passive+no_connect"))
    )
    (net (code "64") (name "unconnected-(X2-HSIn(Rx3n)-PadA30)") (class "Default")
      (node (ref "X2") (pin "A30") (pinfunction "HSIn(Rx3n)_A30") (pintype "passive+no_connect"))
    )
    (net (code "65") (name "unconnected-(X2-HSIp(Rx2p)-PadA25)") (class "Default")
      (node (ref "X2") (pin "A25") (pinfunction "HSIp(Rx2p)_A25") (pintype "passive+no_connect"))
    )
    (net (code "66") (name "unconnected-(X2-HSIp(Rx3p)-PadA29)") (class "Default")
      (node (ref "X2") (pin "A29") (pinfunction "HSIp(Rx3p)_A29") (pintype "passive+no_connect"))
    )
    (net (code "67") (name "unconnected-(X2-HSOn(Tx2n)-PadB24)") (class "Default")
      (node (ref "X2") (pin "B24") (pinfunction "HSOn(Tx2n)_B24") (pintype "passive+no_connect"))
    )
    (net (code "68") (name "unconnected-(X2-HSOn(Tx3n)-PadB28)") (class "Default")
      (node (ref "X2") (pin "B28") (pinfunction "HSOn(Tx3n)_B28") (pintype "passive"))
    )
    (net (code "69") (name "unconnected-(X2-HSOp(Tx2p)-PadB23)") (class "Default")
      (node (ref "X2") (pin "B23") (pinfunction "HSOp(Tx2p)_B23") (pintype "passive+no_connect"))
    )
    (net (code "70") (name "unconnected-(X2-HSOp(Tx3p)-PadB27)") (class "Default")
      (node (ref "X2") (pin "B27") (pinfunction "HSOp(Tx3p)_B27") (pintype "passive+no_connect"))
    )
    (net (code "71") (name "unconnected-(X2-JTAG-RST-PadB9)") (class "Default")
      (node (ref "X2") (pin "B9") (pinfunction "JTAG-RST_B9") (pintype "passive+no_connect"))
    )
    (net (code "72") (name "unconnected-(X2-JTAG-TCK-PadA5)") (class "Default")
      (node (ref "X2") (pin "A5") (pinfunction "JTAG-TCK_A5") (pintype "passive+no_connect"))
    )
    (net (code "73") (name "unconnected-(X2-JTAG-TDI-PadA6)") (class "Default")
      (node (ref "X2") (pin "A6") (pinfunction "JTAG-TDI_A6") (pintype "passive+no_connect"))
    )
    (net (code "74") (name "unconnected-(X2-JTAG-TDO-PadA7)") (class "Default")
      (node (ref "X2") (pin "A7") (pinfunction "JTAG-TDO_A7") (pintype "passive+no_connect"))
    )
    (net (code "75") (name "unconnected-(X2-JTAG-TMS-PadA8)") (class "Default")
      (node (ref "X2") (pin "A8") (pinfunction "JTAG-TMS_A8") (pintype "passive+no_connect"))
    )
    (net (code "76") (name "unconnected-(X2-PRSNT#2_(x1)-PadB17)") (class "Default")
      (node (ref "X2") (pin "B17") (pinfunction "PRSNT#2_(x1)_B17") (pintype "passive+no_connect"))
    )
    (net (code "77") (name "unconnected-(X2-Reserved-PadA19)") (class "Default")
      (node (ref "X2") (pin "A19") (pinfunction "Reserved_A19") (pintype "passive+no_connect"))
    )
    (net (code "78") (name "unconnected-(X2-Reserved-PadA32)") (class "Default")
      (node (ref "X2") (pin "A32") (pinfunction "Reserved_A32") (pintype "passive+no_connect"))
    )
    (net (code "79") (name "unconnected-(X2-Reserved-PadB12)") (class "Default")
      (node (ref "X2") (pin "B12") (pinfunction "Reserved_B12") (pintype "passive+no_connect"))
    )
    (net (code "80") (name "unconnected-(X2-Reserved-PadB30)") (class "Default")
      (node (ref "X2") (pin "B30") (pinfunction "Reserved_B30") (pintype "passive+no_connect"))
    )
    (net (code "81") (name "unconnected-(X2-SMBCLK-PadB5)") (class "Default")
      (node (ref "X2") (pin "B5") (pinfunction "SMBCLK_B5") (pintype "passive+no_connect"))
    )
    (net (code "82") (name "unconnected-(X2-SMBDAT-PadB6)") (class "Default")
      (node (ref "X2") (pin "B6") (pinfunction "SMBDAT_B6") (pintype "passive+no_connect"))
    )
    (net (code "83") (name "unconnected-(X2-WAKE#-PadB11)") (class "Default")
      (node (ref "X2") (pin "B11") (pinfunction "WAKE#_B11") (pintype "passive+no_connect"))
    )
    (net (code "84") (name "unconnected-(X5-+1.5V-Pad6)") (class "Default")
      (node (ref "X5") (pin "6") (pinfunction "+1.5V_6") (pintype "passive+no_connect"))
    )
    (net (code "85") (name "unconnected-(X5-+1.5V-Pad28)") (class "Default")
      (node (ref "X5") (pin "28") (pinfunction "+1.5V_28") (pintype "passive+no_connect"))
    )
    (net (code "86") (name "unconnected-(X5-+1.5V-Pad48)") (class "Default")
      (node (ref "X5") (pin "48") (pinfunction "+1.5V_48") (pintype "passive+no_connect"))
    )
    (net (code "87") (name "unconnected-(X5-+3.3Vaux-Pad24)") (class "Default")
      (node (ref "X5") (pin "24") (pinfunction "+3.3Vaux_24") (pintype "passive+no_connect"))
    )
    (net (code "88") (name "unconnected-(X5-CLKREQ#-Pad7)") (class "Default")
      (node (ref "X5") (pin "7") (pinfunction "CLKREQ#_7") (pintype "passive+no_connect"))
    )
    (net (code "89") (name "unconnected-(X5-UIM_VPP-Pad16)") (class "Default")
      (node (ref "X5") (pin "16") (pinfunction "UIM_VPP_16") (pintype "passive+no_connect"))
    )
    (net (code "90") (name "unconnected-(X5-WAKE#-Pad1)") (class "Default")
      (node (ref "X5") (pin "1") (pinfunction "WAKE#_1") (pintype "passive+no_connect"))
    )
    (net (code "91") (name "unconnected-(X9-PRES-Pad8)") (class "Default")
      (node (ref "X9") (pin "8") (pinfunction "PRES_8") (pintype "passive+no_connect"))
    )
    (net (code "92") (name "unconnected-(X9-VPP-Pad6)") (class "Default")
      (node (ref "X9") (pin "6") (pinfunction "VPP_6") (pintype "passive+no_connect"))
    )
  )
)
